# Spindle_Sync.net
KiCad netlist of a schematic drawn in Altium Designer
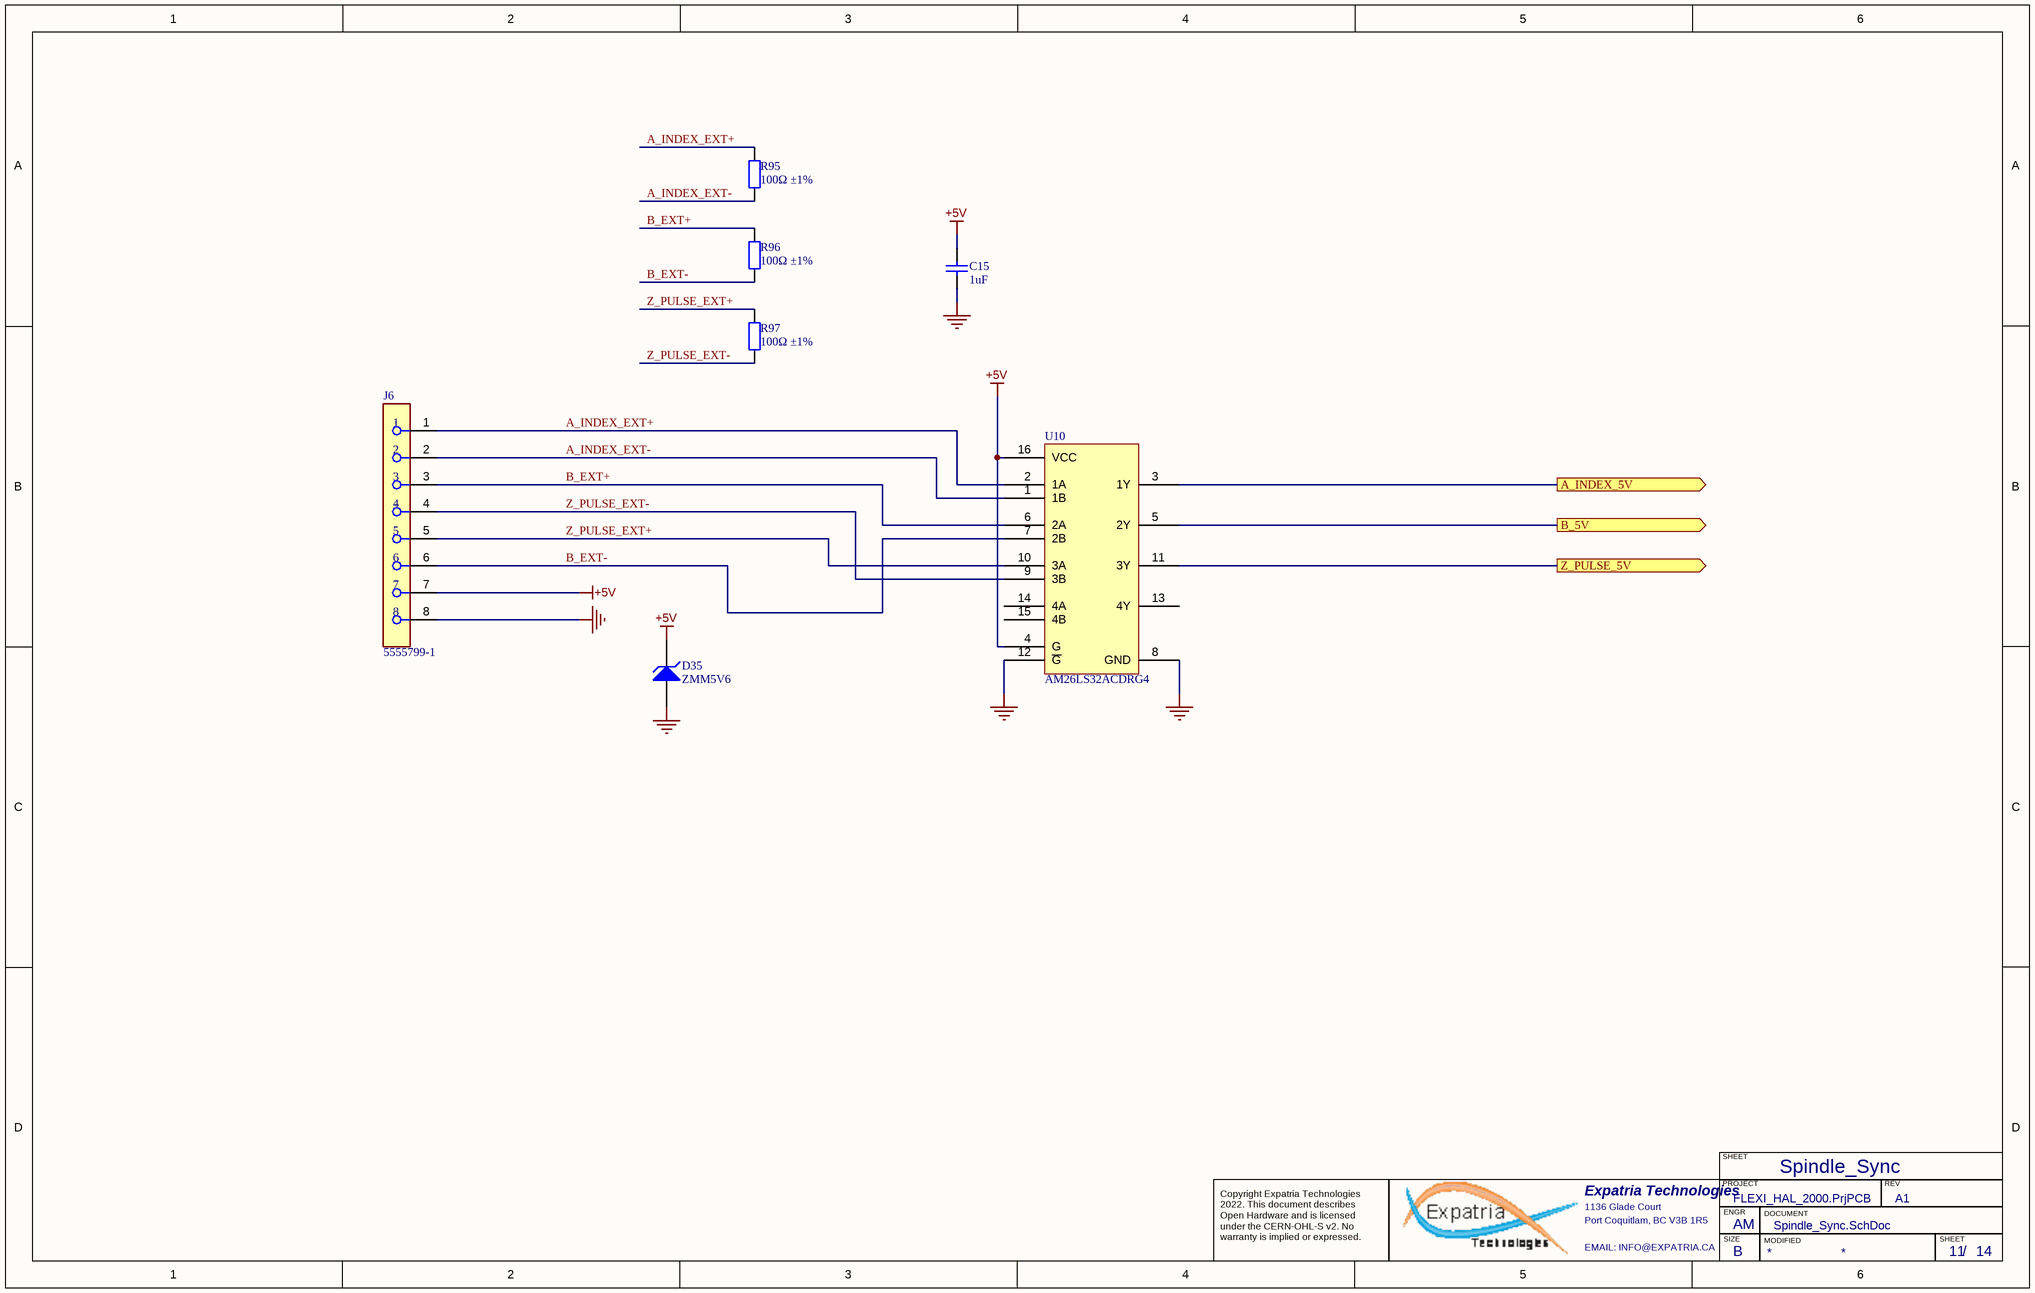
[diagram p0: Spindle_Sync.SchDoc]

(export (version "E")
  (design (tool "Eeschema 10.0.6"))
  (components
    (comp (ref "C15")
      (value "1uF")
      (footprint "0603_C")
      (description "Chip capacitors")
      (fields
        (field (name "MANUFACTURER") "Samsung Electro-Mechanics")
        (field (name "PARTNUMBER") "CL10A105KB8NNNC")
      )
      (libsource (lib "Cap") (part "0603 1uF (105) 10% 50V"))
    )
    (comp (ref "D35")
      (value "ZMM5V6")
      (footprint "LL-34")
      (description "500mW - 0.1uA @ 1V 5.6V LL-34 Zener Diodes ROHS")
      (libsource (lib "Zener") (part "LL-34 ZMM5V6"))
    )
    (comp (ref "J6")
      (value "5555799-1")
      (footprint "FP-5555799-1-MFG")
      (description "CONN MOD JACK 8P8C VERT UNSHLD")
      (fields
        (field (name "MANUFACTURER") "TE Connectivity")
        (field (name "OCTOPART") "https://octopart.com/5555799-1-te+connectivity-39526335")
      )
      (libsource (lib "Altium Content Vault") (part "a32a9c29f5c2290c50060dfb8ad7212"))
    )
    (comp (ref "R95")
      (value "100Ω ±1%")
      (footprint "0603_R")
      (description "Chip resistor")
      (fields (field (name "MANUFACTURER") "Uniroyal Elec") (field (name "PARTNUMBER") "0603WAF1000T5E"))
      (libsource (lib "RES") (part "0603 100R (1000) 1%"))
    )
    (comp (ref "R96")
      (value "100Ω ±1%")
      (footprint "0603_R")
      (description "Chip resistor")
      (fields (field (name "MANUFACTURER") "Uniroyal Elec") (field (name "PARTNUMBER") "0603WAF1000T5E"))
      (libsource (lib "RES") (part "0603 100R (1000) 1%"))
    )
    (comp (ref "R97")
      (value "100Ω ±1%")
      (footprint "0603_R")
      (description "Chip resistor")
      (fields (field (name "MANUFACTURER") "Uniroyal Elec") (field (name "PARTNUMBER") "0603WAF1000T5E"))
      (libsource (lib "RES") (part "0603 100R (1000) 1%"))
    )
    (comp (ref "U10")
      (value "AM26LS32ACDRG4")
      (footprint "SOIC-16_150mil")
      (description "RS-422 Interface IC Quad Diff Line Rcvr")
      (libsource (lib "IC") (part "AM26LS32ACDRG4_[C6180]"))
    )
  )
  (nets
    (net (code "1") (name "+5V") (class "Default")
      (node (ref "C15") (pin "2") (pinfunction "2_2") (pintype "passive"))
      (node (ref "D35") (pin "2") (pinfunction "K_2") (pintype "passive"))
      (node (ref "J6") (pin "7") (pinfunction "7_7") (pintype "passive"))
      (node (ref "U10") (pin "16") (pinfunction "VCC_16") (pintype "passive"))
      (node (ref "U10") (pin "4") (pinfunction "G_4") (pintype "passive"))
    )
    (net (code "2") (name "/A_INDEX_5V") (class "Default")
      (node (ref "U10") (pin "3") (pinfunction "1Y_3") (pintype "passive"))
    )
    (net (code "3") (name "/A_INDEX_EXT+") (class "Default")
      (node (ref "J6") (pin "1") (pinfunction "1_1") (pintype "passive"))
      (node (ref "R95") (pin "2") (pinfunction "2_2") (pintype "passive"))
      (node (ref "U10") (pin "2") (pinfunction "1A_2") (pintype "passive"))
    )
    (net (code "4") (name "/A_INDEX_EXT-") (class "Default")
      (node (ref "J6") (pin "2") (pinfunction "2_2") (pintype "passive"))
      (node (ref "R95") (pin "1") (pinfunction "1_1") (pintype "passive"))
      (node (ref "U10") (pin "1") (pinfunction "1B_1") (pintype "passive"))
    )
    (net (code "5") (name "/B_5V") (class "Default")
      (node (ref "U10") (pin "5") (pinfunction "2Y_5") (pintype "passive"))
    )
    (net (code "6") (name "/B_EXT+") (class "Default")
      (node (ref "J6") (pin "3") (pinfunction "3_3") (pintype "passive"))
      (node (ref "R96") (pin "2") (pinfunction "2_2") (pintype "passive"))
      (node (ref "U10") (pin "6") (pinfunction "2A_6") (pintype "passive"))
    )
    (net (code "7") (name "/B_EXT-") (class "Default")
      (node (ref "J6") (pin "6") (pinfunction "6_6") (pintype "passive"))
      (node (ref "R96") (pin "1") (pinfunction "1_1") (pintype "passive"))
      (node (ref "U10") (pin "7") (pinfunction "2B_7") (pintype "passive"))
    )
    (net (code "8") (name "/Z_PULSE_5V") (class "Default")
      (node (ref "U10") (pin "11") (pinfunction "3Y_11") (pintype "passive"))
    )
    (net (code "9") (name "/Z_PULSE_EXT+") (class "Default")
      (node (ref "J6") (pin "5") (pinfunction "5_5") (pintype "passive"))
      (node (ref "R97") (pin "2") (pinfunction "2_2") (pintype "passive"))
      (node (ref "U10") (pin "10") (pinfunction "3A_10") (pintype "passive"))
    )
    (net (code "10") (name "/Z_PULSE_EXT-") (class "Default")
      (node (ref "J6") (pin "4") (pinfunction "4_4") (pintype "passive"))
      (node (ref "R97") (pin "1") (pinfunction "1_1") (pintype "passive"))
      (node (ref "U10") (pin "9") (pinfunction "3B_9") (pintype "passive"))
    )
    (net (code "11") (name "GND") (class "Default")
      (node (ref "C15") (pin "1") (pinfunction "1_1") (pintype "passive"))
      (node (ref "D35") (pin "1") (pinfunction "A_1") (pintype "passive"))
      (node (ref "J6") (pin "8") (pinfunction "8_8") (pintype "passive"))
      (node (ref "U10") (pin "12") (pinfunction "~{G}_12") (pintype "passive"))
      (node (ref "U10") (pin "8") (pinfunction "GND_8") (pintype "passive"))
    )
    (net (code "12") (name "unconnected-(U10-4A-Pad14)") (class "Default")
      (node (ref "U10") (pin "14") (pinfunction "4A_14") (pintype "passive"))
    )
    (net (code "13") (name "unconnected-(U10-4B-Pad15)") (class "Default")
      (node (ref "U10") (pin "15") (pinfunction "4B_15") (pintype "passive"))
    )
    (net (code "14") (name "unconnected-(U10-4Y-Pad13)") (class "Default")
      (node (ref "U10") (pin "13") (pinfunction "4Y_13") (pintype "passive"))
    )
  )
)
